# LinienRoboter_V2-1_copy.net
KiCad netlist of a schematic drawn in EasyEDA
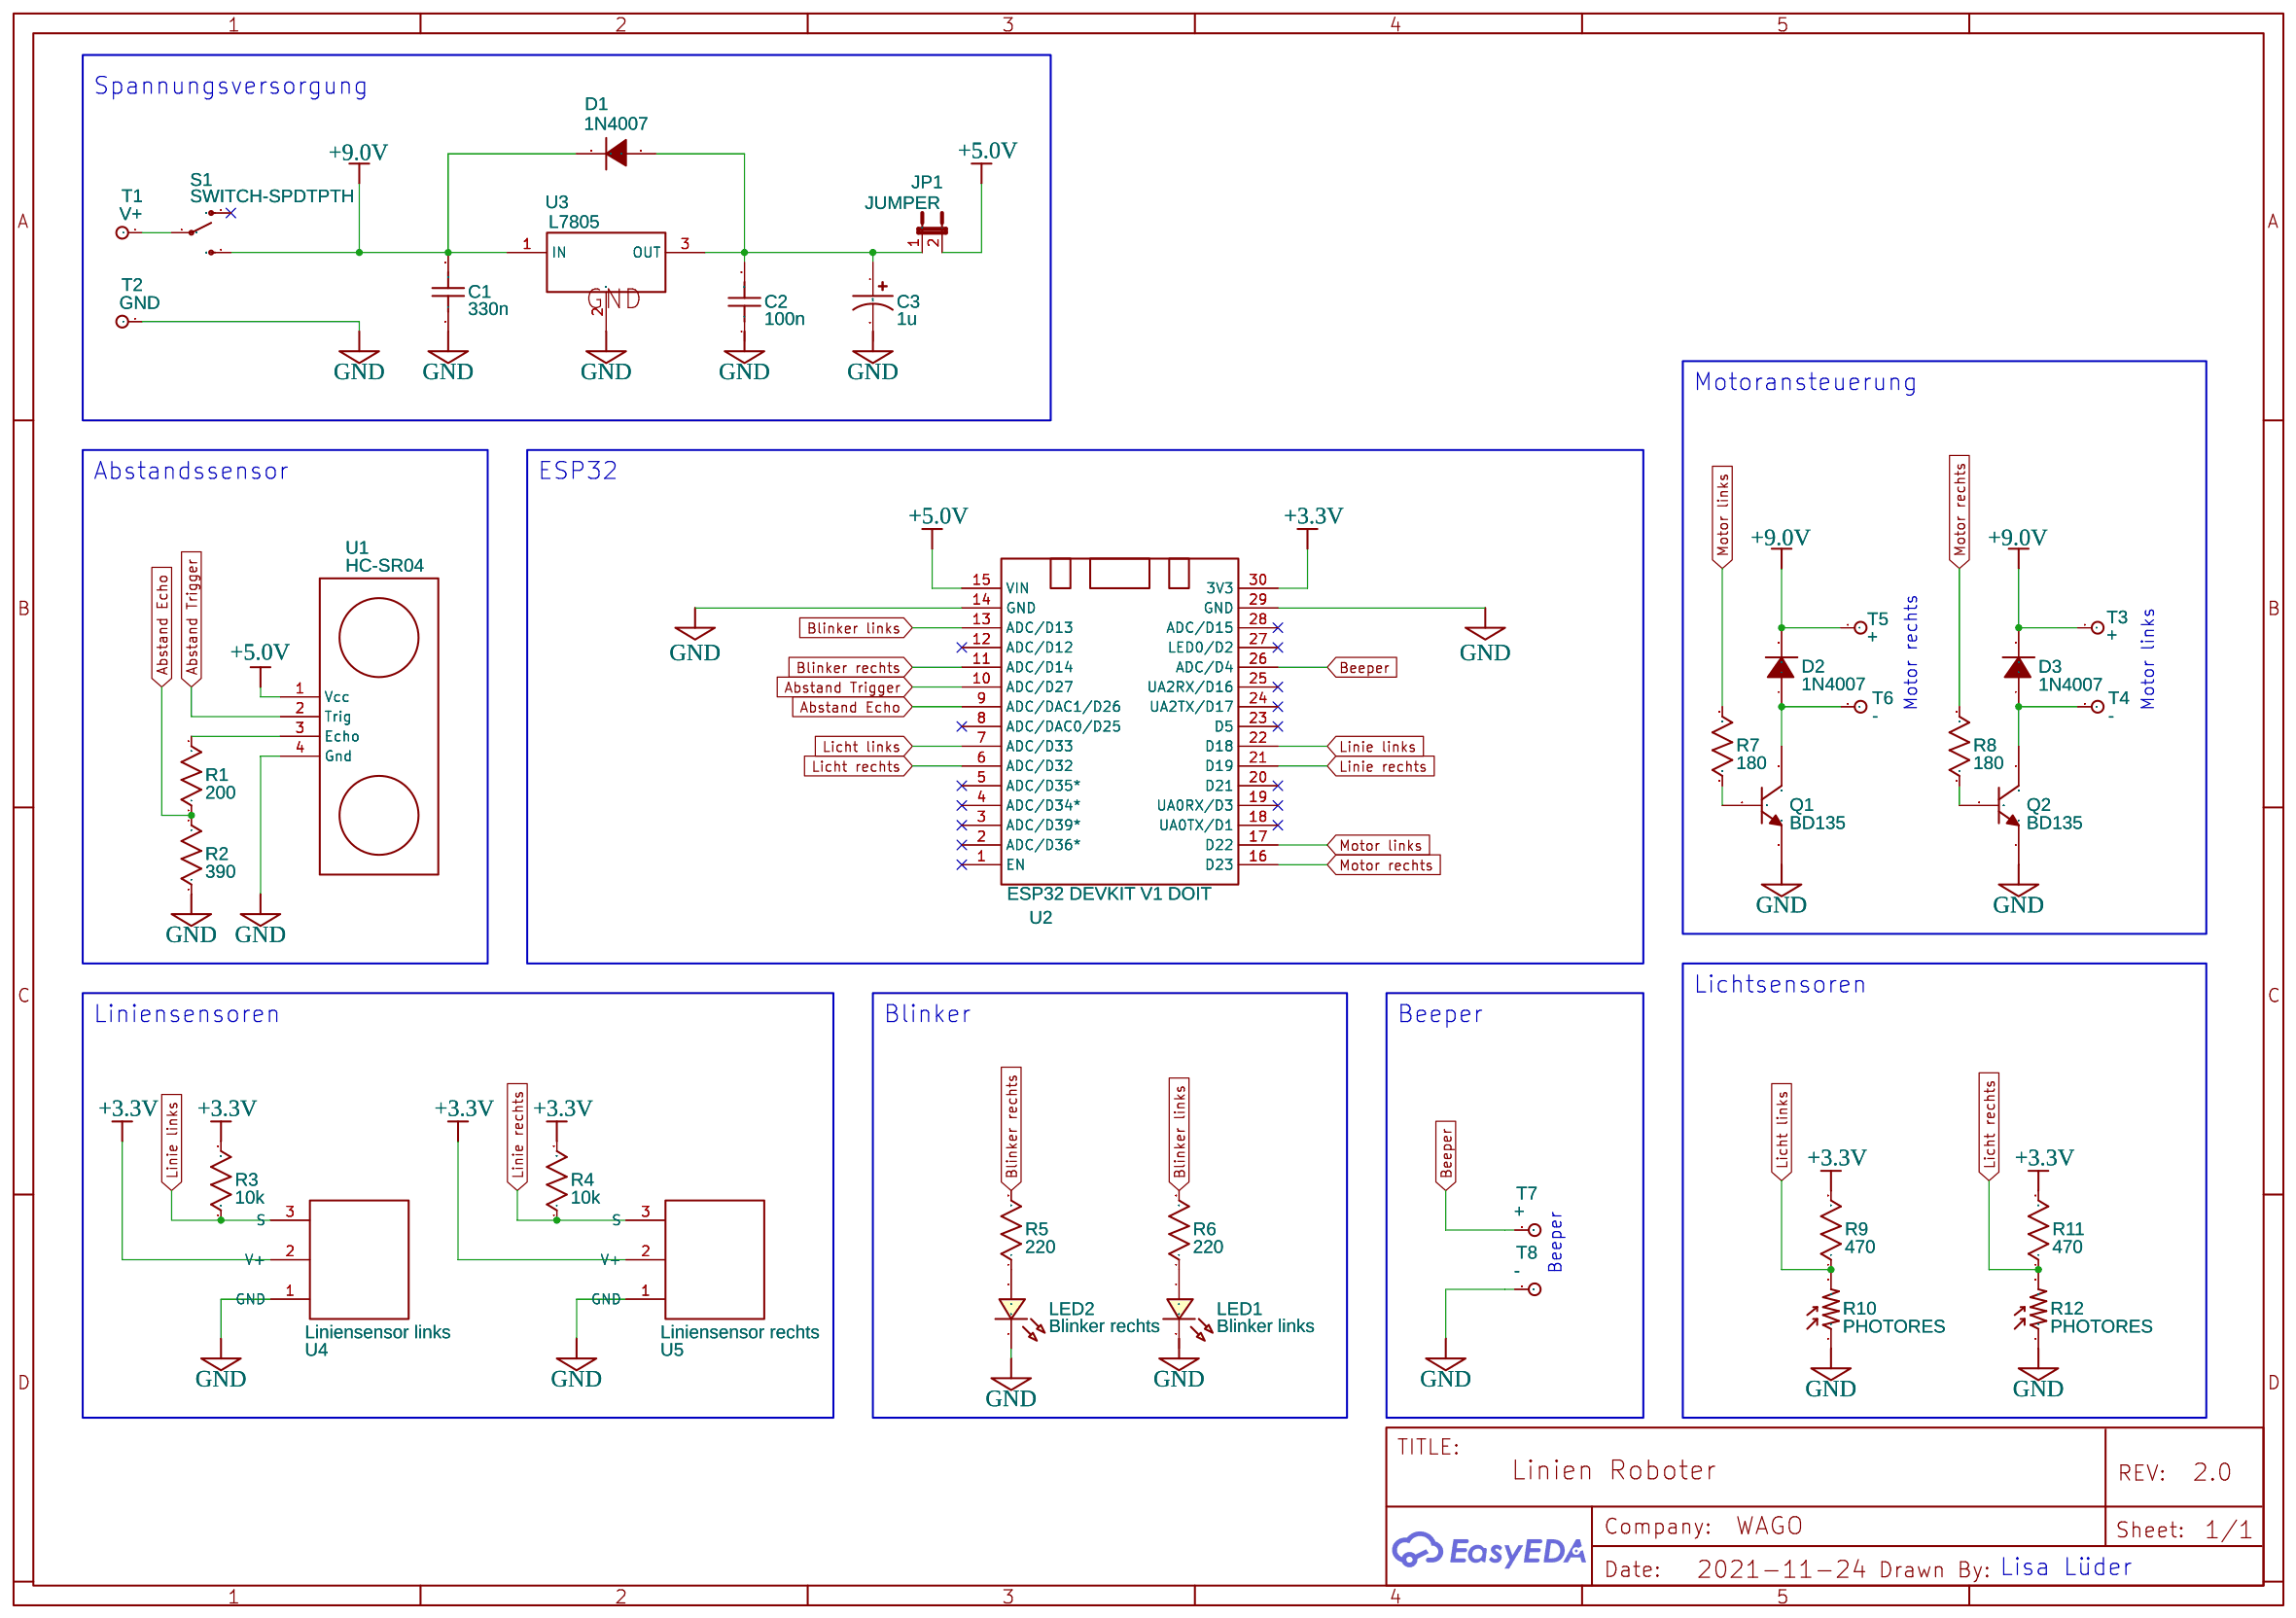
[diagram p0: schematic sheet]

(export (version "E")
  (design (tool "Eeschema 10.0.6"))
  (components
    (comp (ref "C1") (value "330n") (libsource (lib "") (part "C_RAD-0.1_US")))
    (comp (ref "C2") (value "100n") (libsource (lib "") (part "C_RAD-0.1_US")))
    (comp (ref "C3") (value "1u") (libsource (lib "") (part "CE_TH_D6.3×F2.5_US")))
    (comp (ref "D1")
      (value "1N4007")
      (fields (field (name "BOM_Manufacturer Part") "1N4148") (field (name "BOM_Supplier Part") "C14516"))
      (libsource (lib "") (part "1N4148_1"))
    )
    (comp (ref "D2")
      (value "1N4007")
      (fields (field (name "BOM_Manufacturer Part") "1N4148") (field (name "BOM_Supplier Part") "C14516"))
      (libsource (lib "") (part "1N4148"))
    )
    (comp (ref "D3")
      (value "1N4007")
      (fields (field (name "BOM_Manufacturer Part") "1N4148") (field (name "BOM_Supplier Part") "C14516"))
      (libsource (lib "") (part "1N4148"))
    )
    (comp (ref "JP1") (value "JUMPER") (libsource (lib "") (part "JUMPER 2")))
    (comp (ref "LED1")
      (value "Blinker links")
      (fields
        (field (name "BOM_Manufacturer Part") "333-2SURD/S530-A3")
        (field (name "BOM_Supplier Part") "C87271")
      )
      (libsource (lib "") (part "LED-TH-5mm_R"))
    )
    (comp (ref "LED2")
      (value "Blinker rechts")
      (fields
        (field (name "BOM_Manufacturer Part") "333-2SURD/S530-A3")
        (field (name "BOM_Supplier Part") "C87271")
      )
      (libsource (lib "") (part "LED-TH-5mm_R"))
    )
    (comp (ref "Q1")
      (value "BD135")
      (fields (field (name "BOM_Supplier Part") "C283398"))
      (libsource (lib "") (part "BD135"))
    )
    (comp (ref "Q2")
      (value "BD135")
      (fields (field (name "BOM_Supplier Part") "C283398"))
      (libsource (lib "") (part "BD135"))
    )
    (comp (ref "R1") (value "200") (libsource (lib "") (part "R_AXIAL-0.4_US")))
    (comp (ref "R2") (value "390") (libsource (lib "") (part "R_AXIAL-0.4_US")))
    (comp (ref "R3") (value "10k") (libsource (lib "") (part "R_AXIAL-0.4_US")))
    (comp (ref "R4") (value "10k") (libsource (lib "") (part "R_AXIAL-0.4_US")))
    (comp (ref "R5") (value "220") (libsource (lib "") (part "R_AXIAL-0.4_US")))
    (comp (ref "R6") (value "220") (libsource (lib "") (part "R_AXIAL-0.4_US")))
    (comp (ref "R7") (value "180") (libsource (lib "") (part "R_AXIAL-0.4_US")))
    (comp (ref "R8") (value "180") (libsource (lib "") (part "R_AXIAL-0.4_US")))
    (comp (ref "R9") (value "470") (libsource (lib "") (part "R_AXIAL-0.4_US")))
    (comp (ref "R10") (value "PHOTORES") (libsource (lib "") (part "PHOTORESPDV-P9")))
    (comp (ref "R11") (value "470") (libsource (lib "") (part "R_AXIAL-0.4_US")))
    (comp (ref "R12") (value "PHOTORES") (libsource (lib "") (part "PHOTORESPDV-P9")))
    (comp (ref "S1") (value "SWITCH-SPDTPTH") (libsource (lib "") (part "SWITCH-SPDTPTH")))
    (comp (ref "T1") (value "V+") (libsource (lib "") (part "PAD")))
    (comp (ref "T2") (value "GND") (libsource (lib "") (part "PAD")))
    (comp (ref "T3") (value "+") (libsource (lib "") (part "PAD_1")))
    (comp (ref "T4") (value "-") (libsource (lib "") (part "PAD_1")))
    (comp (ref "T5") (value "+") (libsource (lib "") (part "PAD_1")))
    (comp (ref "T6") (value "-") (libsource (lib "") (part "PAD_1")))
    (comp (ref "T7") (value "+") (libsource (lib "") (part "PAD_1")))
    (comp (ref "T8") (value "-") (libsource (lib "") (part "PAD_1")))
    (comp (ref "U1") (value "HC-SR04") (libsource (lib "") (part "HC-SR04")))
    (comp (ref "U2") (value "ESP32 DEVKIT V1 DOIT") (libsource (lib "") (part "ESP32 DEVKIT V1 DOIT")))
    (comp (ref "U3")
      (value "L7805")
      (fields (field (name "BOM_Manufacturer Part") "L7805CV-DG") (field (name "BOM_Supplier Part") "C3795"))
      (libsource (lib "") (part "7805(TO-220)"))
    )
    (comp (ref "U4") (value "Liniensensor links") (libsource (lib "") (part "Liniensensor")))
    (comp (ref "U5") (value "Liniensensor rechts") (libsource (lib "") (part "Liniensensor")))
  )
  (nets
    (net (code "1") (name "+3.3V") (class "Default")
      (node (ref "R11") (pin "2") (pinfunction "2_2") (pintype "unspecified"))
      (node (ref "R3") (pin "2") (pinfunction "2_2") (pintype "unspecified"))
      (node (ref "R4") (pin "2") (pinfunction "2_2") (pintype "unspecified"))
      (node (ref "R9") (pin "2") (pinfunction "2_2") (pintype "unspecified"))
      (node (ref "U2") (pin "30") (pinfunction "3V3_30") (pintype "bidirectional"))
      (node (ref "U4") (pin "2") (pinfunction "V+_2") (pintype "unspecified"))
      (node (ref "U5") (pin "2") (pinfunction "V+_2") (pintype "unspecified"))
    )
    (net (code "2") (name "+5.0V") (class "Default")
      (node (ref "JP1") (pin "2") (pinfunction "-_2") (pintype "unspecified"))
      (node (ref "U1") (pin "1") (pinfunction "Vcc_1") (pintype "unspecified"))
      (node (ref "U2") (pin "15") (pinfunction "VIN_15") (pintype "input"))
    )
    (net (code "3") (name "+9.0V") (class "Default")
      (node (ref "C1") (pin "2") (pinfunction "2_2") (pintype "unspecified"))
      (node (ref "D1") (pin "2") (pinfunction "C_2") (pintype "unspecified"))
      (node (ref "D2") (pin "2") (pinfunction "C_2") (pintype "unspecified"))
      (node (ref "D3") (pin "2") (pinfunction "C_2") (pintype "unspecified"))
      (node (ref "S1") (pin "3") (pinfunction "S_3") (pintype "unspecified"))
      (node (ref "T3") (pin "1") (pinfunction "1_1") (pintype "unspecified"))
      (node (ref "T5") (pin "1") (pinfunction "1_1") (pintype "unspecified"))
      (node (ref "U3") (pin "1") (pinfunction "IN_1") (pintype "passive"))
    )
    (net (code "4") (name "Abstand Echo") (class "Default")
      (node (ref "R1") (pin "1") (pinfunction "1_1") (pintype "unspecified"))
      (node (ref "R2") (pin "2") (pinfunction "2_2") (pintype "unspecified"))
      (node (ref "U2") (pin "9") (pinfunction "ADC/DAC1/D26_9") (pintype "bidirectional"))
    )
    (net (code "5") (name "Abstand Trigger") (class "Default")
      (node (ref "U1") (pin "2") (pinfunction "Trig_2") (pintype "unspecified"))
      (node (ref "U2") (pin "10") (pinfunction "ADC/D27_10") (pintype "bidirectional"))
    )
    (net (code "6") (name "Beeper") (class "Default")
      (node (ref "T7") (pin "1") (pinfunction "1_1") (pintype "unspecified"))
      (node (ref "U2") (pin "26") (pinfunction "ADC/D4_26") (pintype "bidirectional"))
    )
    (net (code "7") (name "Blinker links") (class "Default")
      (node (ref "R6") (pin "2") (pinfunction "2_2") (pintype "unspecified"))
      (node (ref "U2") (pin "13") (pinfunction "ADC/D13_13") (pintype "bidirectional"))
    )
    (net (code "8") (name "Blinker rechts") (class "Default")
      (node (ref "R5") (pin "2") (pinfunction "2_2") (pintype "unspecified"))
      (node (ref "U2") (pin "11") (pinfunction "ADC/D14_11") (pintype "bidirectional"))
    )
    (net (code "9") (name "GND") (class "Default")
      (node (ref "C1") (pin "1") (pinfunction "1_1") (pintype "unspecified"))
      (node (ref "C2") (pin "1") (pinfunction "1_1") (pintype "unspecified"))
      (node (ref "C3") (pin "2") (pinfunction "2_2") (pintype "unspecified"))
      (node (ref "LED1") (pin "2") (pinfunction "2_2") (pintype "unspecified"))
      (node (ref "LED2") (pin "2") (pinfunction "2_2") (pintype "unspecified"))
      (node (ref "Q1") (pin "1") (pinfunction "E_1") (pintype "unspecified"))
      (node (ref "Q2") (pin "1") (pinfunction "E_1") (pintype "unspecified"))
      (node (ref "R10") (pin "1") (pinfunction "1_1") (pintype "unspecified"))
      (node (ref "R12") (pin "1") (pinfunction "1_1") (pintype "unspecified"))
      (node (ref "R2") (pin "1") (pinfunction "1_1") (pintype "unspecified"))
      (node (ref "T2") (pin "1") (pinfunction "1_1") (pintype "unspecified"))
      (node (ref "T8") (pin "1") (pinfunction "1_1") (pintype "unspecified"))
      (node (ref "U1") (pin "4") (pinfunction "Gnd_4") (pintype "unspecified"))
      (node (ref "U2") (pin "14") (pinfunction "GND_14") (pintype "bidirectional"))
      (node (ref "U2") (pin "29") (pinfunction "GND_29") (pintype "bidirectional"))
      (node (ref "U3") (pin "2") (pinfunction "GND_2") (pintype "passive"))
      (node (ref "U4") (pin "1") (pinfunction "GND_1") (pintype "unspecified"))
      (node (ref "U5") (pin "1") (pinfunction "GND_1") (pintype "unspecified"))
    )
    (net (code "10") (name "Licht links") (class "Default")
      (node (ref "R10") (pin "2") (pinfunction "2_2") (pintype "unspecified"))
      (node (ref "R9") (pin "1") (pinfunction "1_1") (pintype "unspecified"))
      (node (ref "U2") (pin "7") (pinfunction "ADC/D33_7") (pintype "bidirectional"))
    )
    (net (code "11") (name "Licht rechts") (class "Default")
      (node (ref "R11") (pin "1") (pinfunction "1_1") (pintype "unspecified"))
      (node (ref "R12") (pin "2") (pinfunction "2_2") (pintype "unspecified"))
      (node (ref "U2") (pin "6") (pinfunction "ADC/D32_6") (pintype "bidirectional"))
    )
    (net (code "12") (name "Linie links") (class "Default")
      (node (ref "R3") (pin "1") (pinfunction "1_1") (pintype "unspecified"))
      (node (ref "U2") (pin "22") (pinfunction "D18_22") (pintype "bidirectional"))
      (node (ref "U4") (pin "3") (pinfunction "S_3") (pintype "unspecified"))
    )
    (net (code "13") (name "Linie rechts") (class "Default")
      (node (ref "R4") (pin "1") (pinfunction "1_1") (pintype "unspecified"))
      (node (ref "U2") (pin "21") (pinfunction "D19_21") (pintype "bidirectional"))
      (node (ref "U5") (pin "3") (pinfunction "S_3") (pintype "unspecified"))
    )
    (net (code "14") (name "Motor links") (class "Default")
      (node (ref "R7") (pin "2") (pinfunction "2_2") (pintype "unspecified"))
      (node (ref "U2") (pin "17") (pinfunction "D22_17") (pintype "bidirectional"))
    )
    (net (code "15") (name "Motor rechts") (class "Default")
      (node (ref "R8") (pin "2") (pinfunction "2_2") (pintype "unspecified"))
      (node (ref "U2") (pin "16") (pinfunction "D23_16") (pintype "bidirectional"))
    )
    (net (code "16") (name "Net-(D1-A)") (class "Default")
      (node (ref "C2") (pin "2") (pinfunction "2_2") (pintype "unspecified"))
      (node (ref "C3") (pin "1") (pinfunction "1_1") (pintype "unspecified"))
      (node (ref "D1") (pin "1") (pinfunction "A_1") (pintype "unspecified"))
      (node (ref "JP1") (pin "1") (pinfunction "+_1") (pintype "unspecified"))
      (node (ref "U3") (pin "3") (pinfunction "OUT_3") (pintype "passive"))
    )
    (net (code "17") (name "Net-(D2-A)") (class "Default")
      (node (ref "D2") (pin "1") (pinfunction "A_1") (pintype "unspecified"))
      (node (ref "Q1") (pin "2") (pinfunction "C_2") (pintype "unspecified"))
      (node (ref "T6") (pin "1") (pinfunction "1_1") (pintype "unspecified"))
    )
    (net (code "18") (name "Net-(D3-A)") (class "Default")
      (node (ref "D3") (pin "1") (pinfunction "A_1") (pintype "unspecified"))
      (node (ref "Q2") (pin "2") (pinfunction "C_2") (pintype "unspecified"))
      (node (ref "T4") (pin "1") (pinfunction "1_1") (pintype "unspecified"))
    )
    (net (code "19") (name "Net-(LED1-Pad1)") (class "Default")
      (node (ref "LED1") (pin "1") (pinfunction "1_1") (pintype "unspecified"))
      (node (ref "R6") (pin "1") (pinfunction "1_1") (pintype "unspecified"))
    )
    (net (code "20") (name "Net-(LED2-Pad1)") (class "Default")
      (node (ref "LED2") (pin "1") (pinfunction "1_1") (pintype "unspecified"))
      (node (ref "R5") (pin "1") (pinfunction "1_1") (pintype "unspecified"))
    )
    (net (code "21") (name "Net-(Q1-B)") (class "Default")
      (node (ref "Q1") (pin "3") (pinfunction "B_3") (pintype "unspecified"))
      (node (ref "R7") (pin "1") (pinfunction "1_1") (pintype "unspecified"))
    )
    (net (code "22") (name "Net-(Q2-B)") (class "Default")
      (node (ref "Q2") (pin "3") (pinfunction "B_3") (pintype "unspecified"))
      (node (ref "R8") (pin "1") (pinfunction "1_1") (pintype "unspecified"))
    )
    (net (code "23") (name "Net-(S1-P)") (class "Default")
      (node (ref "S1") (pin "2") (pinfunction "P_2") (pintype "unspecified"))
      (node (ref "T1") (pin "1") (pinfunction "1_1") (pintype "unspecified"))
    )
    (net (code "24") (name "Net-(U1-Echo)") (class "Default")
      (node (ref "R1") (pin "2") (pinfunction "2_2") (pintype "unspecified"))
      (node (ref "U1") (pin "3") (pinfunction "Echo_3") (pintype "unspecified"))
    )
    (net (code "25") (name "unconnected-(S1-O-Pad1)") (class "Default")
      (node (ref "S1") (pin "1") (pinfunction "O_1") (pintype "unspecified+no_connect"))
    )
    (net (code "26") (name "unconnected-(U2-ADC{slash}D12-Pad12)") (class "Default")
      (node (ref "U2") (pin "12") (pinfunction "ADC/D12_12") (pintype "bidirectional+no_connect"))
    )
    (net (code "27") (name "unconnected-(U2-ADC{slash}D15-Pad28)") (class "Default")
      (node (ref "U2") (pin "28") (pinfunction "ADC/D15_28") (pintype "bidirectional+no_connect"))
    )
    (net (code "28") (name "unconnected-(U2-ADC{slash}D34*-Pad4)") (class "Default")
      (node (ref "U2") (pin "4") (pinfunction "ADC/D34*_4") (pintype "input+no_connect"))
    )
    (net (code "29") (name "unconnected-(U2-ADC{slash}D35*-Pad5)") (class "Default")
      (node (ref "U2") (pin "5") (pinfunction "ADC/D35*_5") (pintype "input+no_connect"))
    )
    (net (code "30") (name "unconnected-(U2-ADC{slash}D36*-Pad2)") (class "Default")
      (node (ref "U2") (pin "2") (pinfunction "ADC/D36*_2") (pintype "input+no_connect"))
    )
    (net (code "31") (name "unconnected-(U2-ADC{slash}D39*-Pad3)") (class "Default")
      (node (ref "U2") (pin "3") (pinfunction "ADC/D39*_3") (pintype "input+no_connect"))
    )
    (net (code "32") (name "unconnected-(U2-ADC{slash}DAC0{slash}D25-Pad8)") (class "Default")
      (node (ref "U2") (pin "8") (pinfunction "ADC/DAC0/D25_8") (pintype "bidirectional+no_connect"))
    )
    (net (code "33") (name "unconnected-(U2-D5-Pad23)") (class "Default")
      (node (ref "U2") (pin "23") (pinfunction "D5_23") (pintype "bidirectional+no_connect"))
    )
    (net (code "34") (name "unconnected-(U2-D21-Pad20)") (class "Default")
      (node (ref "U2") (pin "20") (pinfunction "D21_20") (pintype "bidirectional+no_connect"))
    )
    (net (code "35") (name "unconnected-(U2-EN-Pad1)") (class "Default")
      (node (ref "U2") (pin "1") (pinfunction "EN_1") (pintype "bidirectional+no_connect"))
    )
    (net (code "36") (name "unconnected-(U2-LED0{slash}D2-Pad27)") (class "Default")
      (node (ref "U2") (pin "27") (pinfunction "LED0/D2_27") (pintype "bidirectional+no_connect"))
    )
    (net (code "37") (name "unconnected-(U2-UA0RX{slash}D3-Pad19)") (class "Default")
      (node (ref "U2") (pin "19") (pinfunction "UA0RX/D3_19") (pintype "bidirectional+no_connect"))
    )
    (net (code "38") (name "unconnected-(U2-UA0TX{slash}D1-Pad18)") (class "Default")
      (node (ref "U2") (pin "18") (pinfunction "UA0TX/D1_18") (pintype "bidirectional+no_connect"))
    )
    (net (code "39") (name "unconnected-(U2-UA2RX{slash}D16-Pad25)") (class "Default")
      (node (ref "U2") (pin "25") (pinfunction "UA2RX/D16_25") (pintype "bidirectional+no_connect"))
    )
    (net (code "40") (name "unconnected-(U2-UA2TX{slash}D17-Pad24)") (class "Default")
      (node (ref "U2") (pin "24") (pinfunction "UA2TX/D17_24") (pintype "bidirectional+no_connect"))
    )
  )
)
